# Panel_Frontal.net
KiCad netlist of a schematic drawn in EAGLE
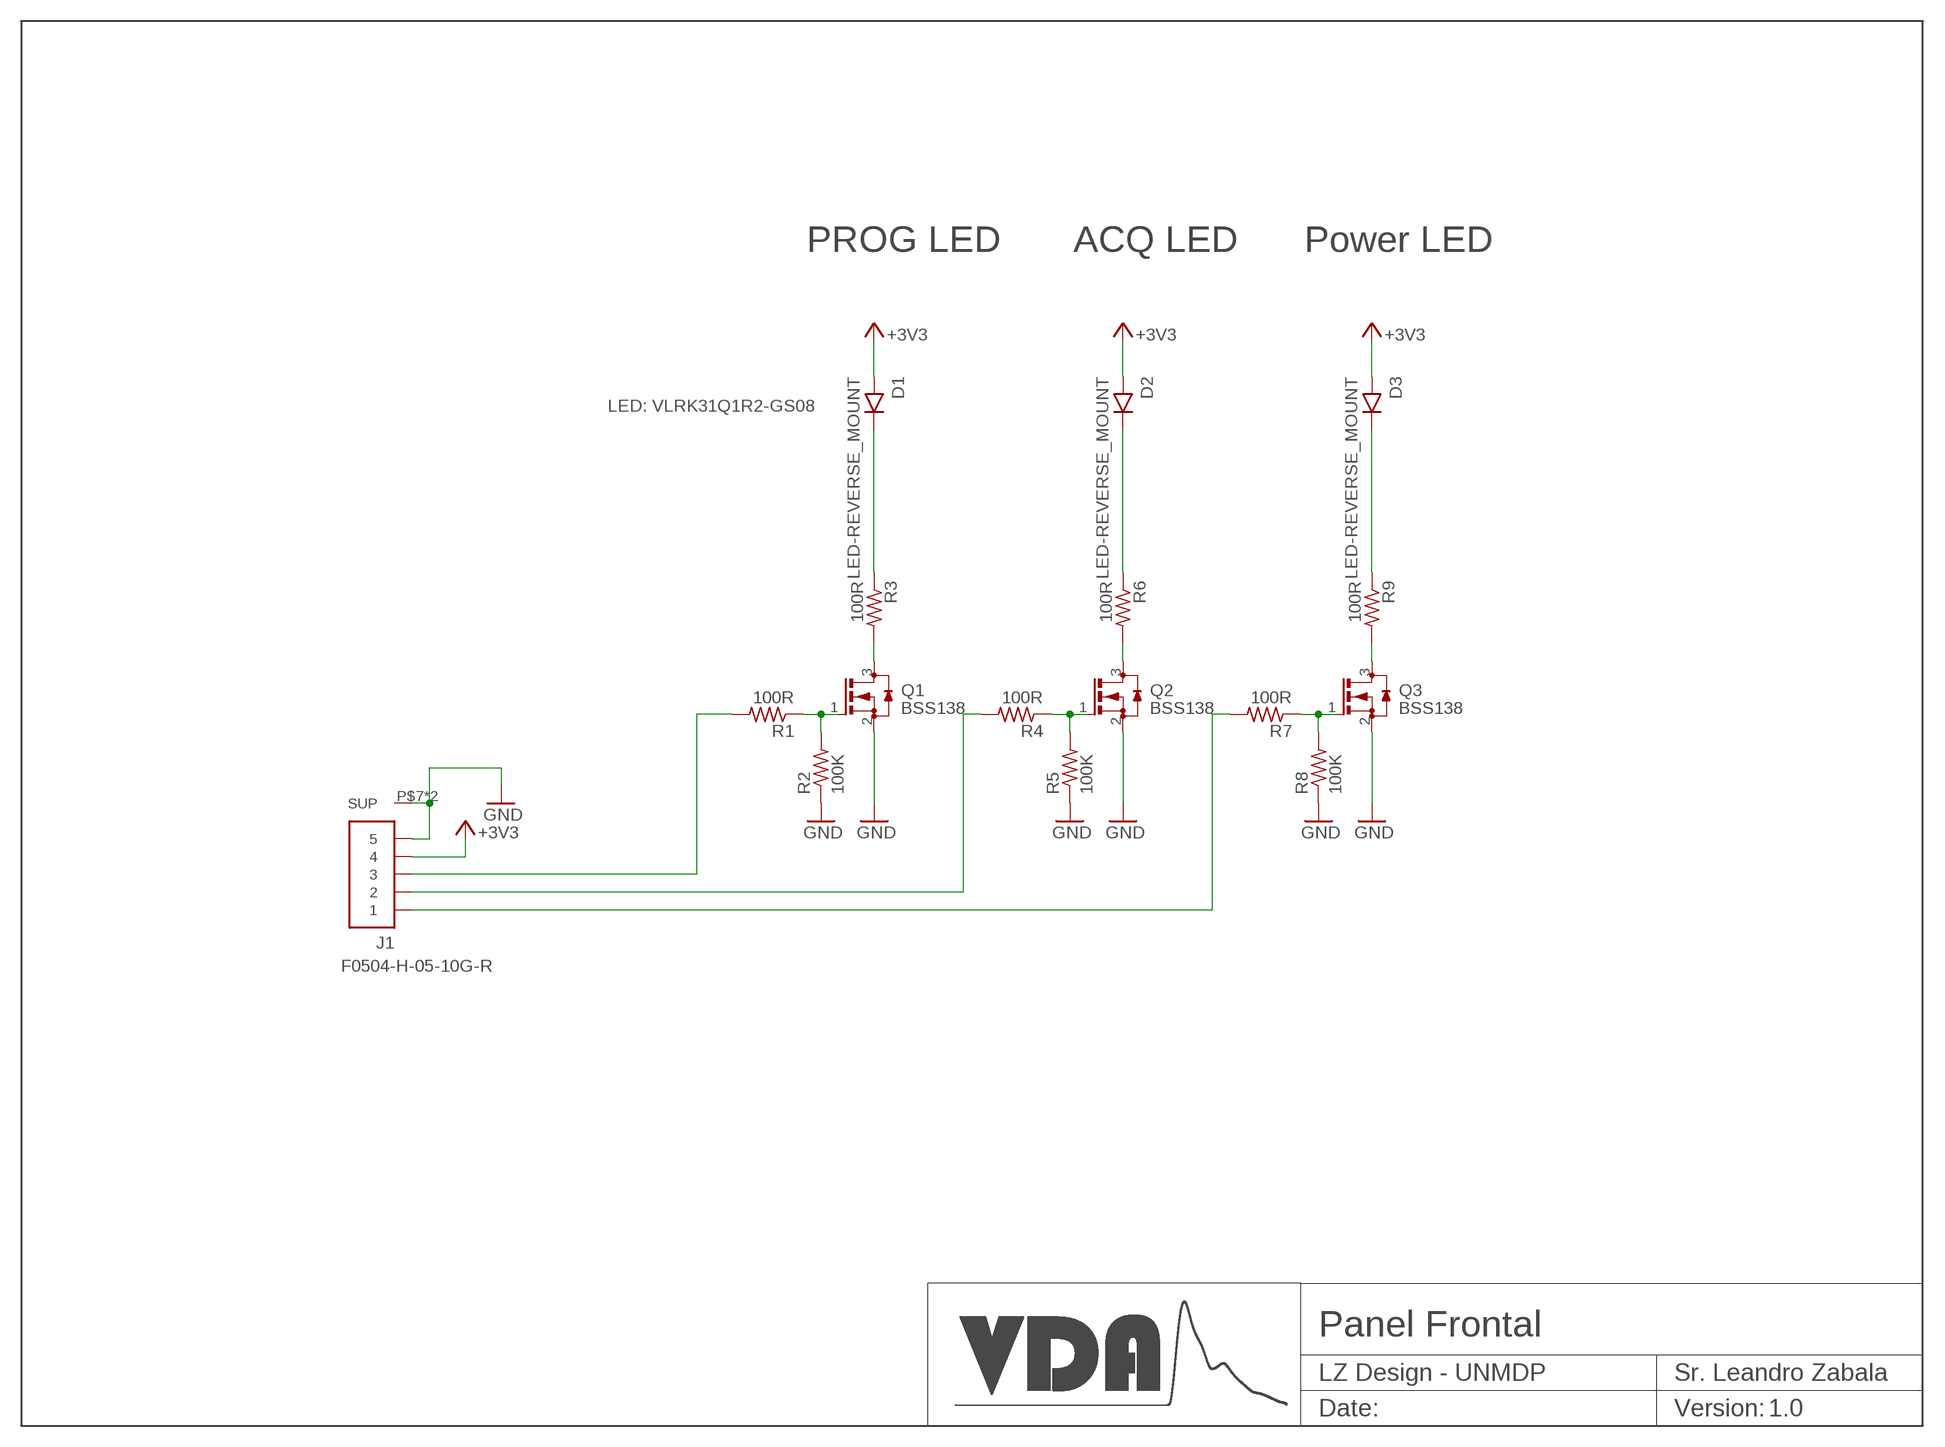
[diagram p0: schematic, sheet 1]

(export (version "E")
  (design (tool "Eeschema 10.0.6"))
  (components
    (comp (ref "D1")
      (value "LED-REVERSE_MOUNT")
      (footprint "eagle-import:VLRK31")
      (libsource (lib "eagle-import") (part "LED-REVERSE_MOUNT"))
    )
    (comp (ref "D2")
      (value "LED-REVERSE_MOUNT")
      (footprint "eagle-import:VLRK31")
      (libsource (lib "eagle-import") (part "LED-REVERSE_MOUNT"))
    )
    (comp (ref "D3")
      (value "LED-REVERSE_MOUNT")
      (footprint "eagle-import:VLRK31")
      (libsource (lib "eagle-import") (part "LED-REVERSE_MOUNT"))
    )
    (comp (ref "J1")
      (value "F0504-H-05-10G-R")
      (footprint "eagle-import:F0504-H-05-10G-R")
      (libsource (lib "eagle-import") (part "F0504-H-05-10G-R"))
    )
    (comp (ref "Q1")
      (value "BSS138")
      (footprint "eagle-import:SOT-23")
      (libsource (lib "eagle-import") (part "N-MOS_SOT23-3"))
    )
    (comp (ref "Q2")
      (value "BSS138")
      (footprint "eagle-import:SOT-23")
      (libsource (lib "eagle-import") (part "N-MOS_SOT23-3"))
    )
    (comp (ref "Q3")
      (value "BSS138")
      (footprint "eagle-import:SOT-23")
      (libsource (lib "eagle-import") (part "N-MOS_SOT23-3"))
    )
    (comp (ref "R1")
      (value "100R")
      (footprint "eagle-import:R_0603")
      (libsource (lib "eagle-import") (part "R_0603"))
    )
    (comp (ref "R2")
      (value "100K")
      (footprint "eagle-import:R_0603")
      (libsource (lib "eagle-import") (part "R_0603"))
    )
    (comp (ref "R3")
      (value "100R")
      (footprint "eagle-import:R_0603")
      (libsource (lib "eagle-import") (part "R_0603"))
    )
    (comp (ref "R4")
      (value "100R")
      (footprint "eagle-import:R_0603")
      (libsource (lib "eagle-import") (part "R_0603"))
    )
    (comp (ref "R5")
      (value "100K")
      (footprint "eagle-import:R_0603")
      (libsource (lib "eagle-import") (part "R_0603"))
    )
    (comp (ref "R6")
      (value "100R")
      (footprint "eagle-import:R_0603")
      (libsource (lib "eagle-import") (part "R_0603"))
    )
    (comp (ref "R7")
      (value "100R")
      (footprint "eagle-import:R_0603")
      (libsource (lib "eagle-import") (part "R_0603"))
    )
    (comp (ref "R8")
      (value "100K")
      (footprint "eagle-import:R_0603")
      (libsource (lib "eagle-import") (part "R_0603"))
    )
    (comp (ref "R9")
      (value "100R")
      (footprint "eagle-import:R_0603")
      (libsource (lib "eagle-import") (part "R_0603"))
    )
  )
  (nets
    (net (code "1") (name "+3V3") (class "Default")
      (node (ref "D1") (pin "A") (pinfunction "A_A") (pintype "bidirectional"))
      (node (ref "D2") (pin "A") (pinfunction "A_A") (pintype "bidirectional"))
      (node (ref "D3") (pin "A") (pinfunction "A_A") (pintype "bidirectional"))
      (node (ref "J1") (pin "P$4") (pinfunction "4_P$4") (pintype "bidirectional"))
    )
    (net (code "2") (name "GND") (class "Default")
      (node (ref "J1") (pin "P$5") (pinfunction "5_P$5") (pintype "bidirectional"))
      (node (ref "J1") (pin "P$7") (pinfunction "SUP_P$7") (pintype "bidirectional"))
      (node (ref "J1") (pin "P$8") (pinfunction "SUP_P$8") (pintype "bidirectional"))
      (node (ref "Q1") (pin "2") (pinfunction "S_2") (pintype "passive"))
      (node (ref "Q2") (pin "2") (pinfunction "S_2") (pintype "passive"))
      (node (ref "Q3") (pin "2") (pinfunction "S_2") (pintype "passive"))
      (node (ref "R2") (pin "1") (pinfunction "1_1") (pintype "passive"))
      (node (ref "R5") (pin "1") (pinfunction "1_1") (pintype "passive"))
      (node (ref "R8") (pin "1") (pinfunction "1_1") (pintype "passive"))
    )
    (net (code "3") (name "Net-(D1-PadK)") (class "Default")
      (node (ref "D1") (pin "K") (pinfunction "K_K") (pintype "bidirectional"))
      (node (ref "R3") (pin "1") (pinfunction "1_1") (pintype "passive"))
    )
    (net (code "4") (name "Net-(D2-PadK)") (class "Default")
      (node (ref "D2") (pin "K") (pinfunction "K_K") (pintype "bidirectional"))
      (node (ref "R6") (pin "1") (pinfunction "1_1") (pintype "passive"))
    )
    (net (code "5") (name "Net-(D3-PadK)") (class "Default")
      (node (ref "D3") (pin "K") (pinfunction "K_K") (pintype "bidirectional"))
      (node (ref "R9") (pin "1") (pinfunction "1_1") (pintype "passive"))
    )
    (net (code "6") (name "Net-(J1-1)") (class "Default")
      (node (ref "J1") (pin "P$1") (pinfunction "1_P$1") (pintype "bidirectional"))
      (node (ref "R7") (pin "2") (pinfunction "2_2") (pintype "passive"))
    )
    (net (code "7") (name "Net-(J1-2)") (class "Default")
      (node (ref "J1") (pin "P$2") (pinfunction "2_P$2") (pintype "bidirectional"))
      (node (ref "R4") (pin "2") (pinfunction "2_2") (pintype "passive"))
    )
    (net (code "8") (name "Net-(J1-3)") (class "Default")
      (node (ref "J1") (pin "P$3") (pinfunction "3_P$3") (pintype "bidirectional"))
      (node (ref "R1") (pin "2") (pinfunction "2_2") (pintype "passive"))
    )
    (net (code "9") (name "Net-(Q1-D)") (class "Default")
      (node (ref "Q1") (pin "3") (pinfunction "D_3") (pintype "passive"))
      (node (ref "R3") (pin "2") (pinfunction "2_2") (pintype "passive"))
    )
    (net (code "10") (name "Net-(Q1-G)") (class "Default")
      (node (ref "Q1") (pin "1") (pinfunction "G_1") (pintype "passive"))
      (node (ref "R1") (pin "1") (pinfunction "1_1") (pintype "passive"))
      (node (ref "R2") (pin "2") (pinfunction "2_2") (pintype "passive"))
    )
    (net (code "11") (name "Net-(Q2-D)") (class "Default")
      (node (ref "Q2") (pin "3") (pinfunction "D_3") (pintype "passive"))
      (node (ref "R6") (pin "2") (pinfunction "2_2") (pintype "passive"))
    )
    (net (code "12") (name "Net-(Q2-G)") (class "Default")
      (node (ref "Q2") (pin "1") (pinfunction "G_1") (pintype "passive"))
      (node (ref "R4") (pin "1") (pinfunction "1_1") (pintype "passive"))
      (node (ref "R5") (pin "2") (pinfunction "2_2") (pintype "passive"))
    )
    (net (code "13") (name "Net-(Q3-D)") (class "Default")
      (node (ref "Q3") (pin "3") (pinfunction "D_3") (pintype "passive"))
      (node (ref "R9") (pin "2") (pinfunction "2_2") (pintype "passive"))
    )
    (net (code "14") (name "Net-(Q3-G)") (class "Default")
      (node (ref "Q3") (pin "1") (pinfunction "G_1") (pintype "passive"))
      (node (ref "R7") (pin "1") (pinfunction "1_1") (pintype "passive"))
      (node (ref "R8") (pin "2") (pinfunction "2_2") (pintype "passive"))
    )
  )
)
